# phMeter_v4_2.net
KiCad netlist of a schematic drawn in EAGLE
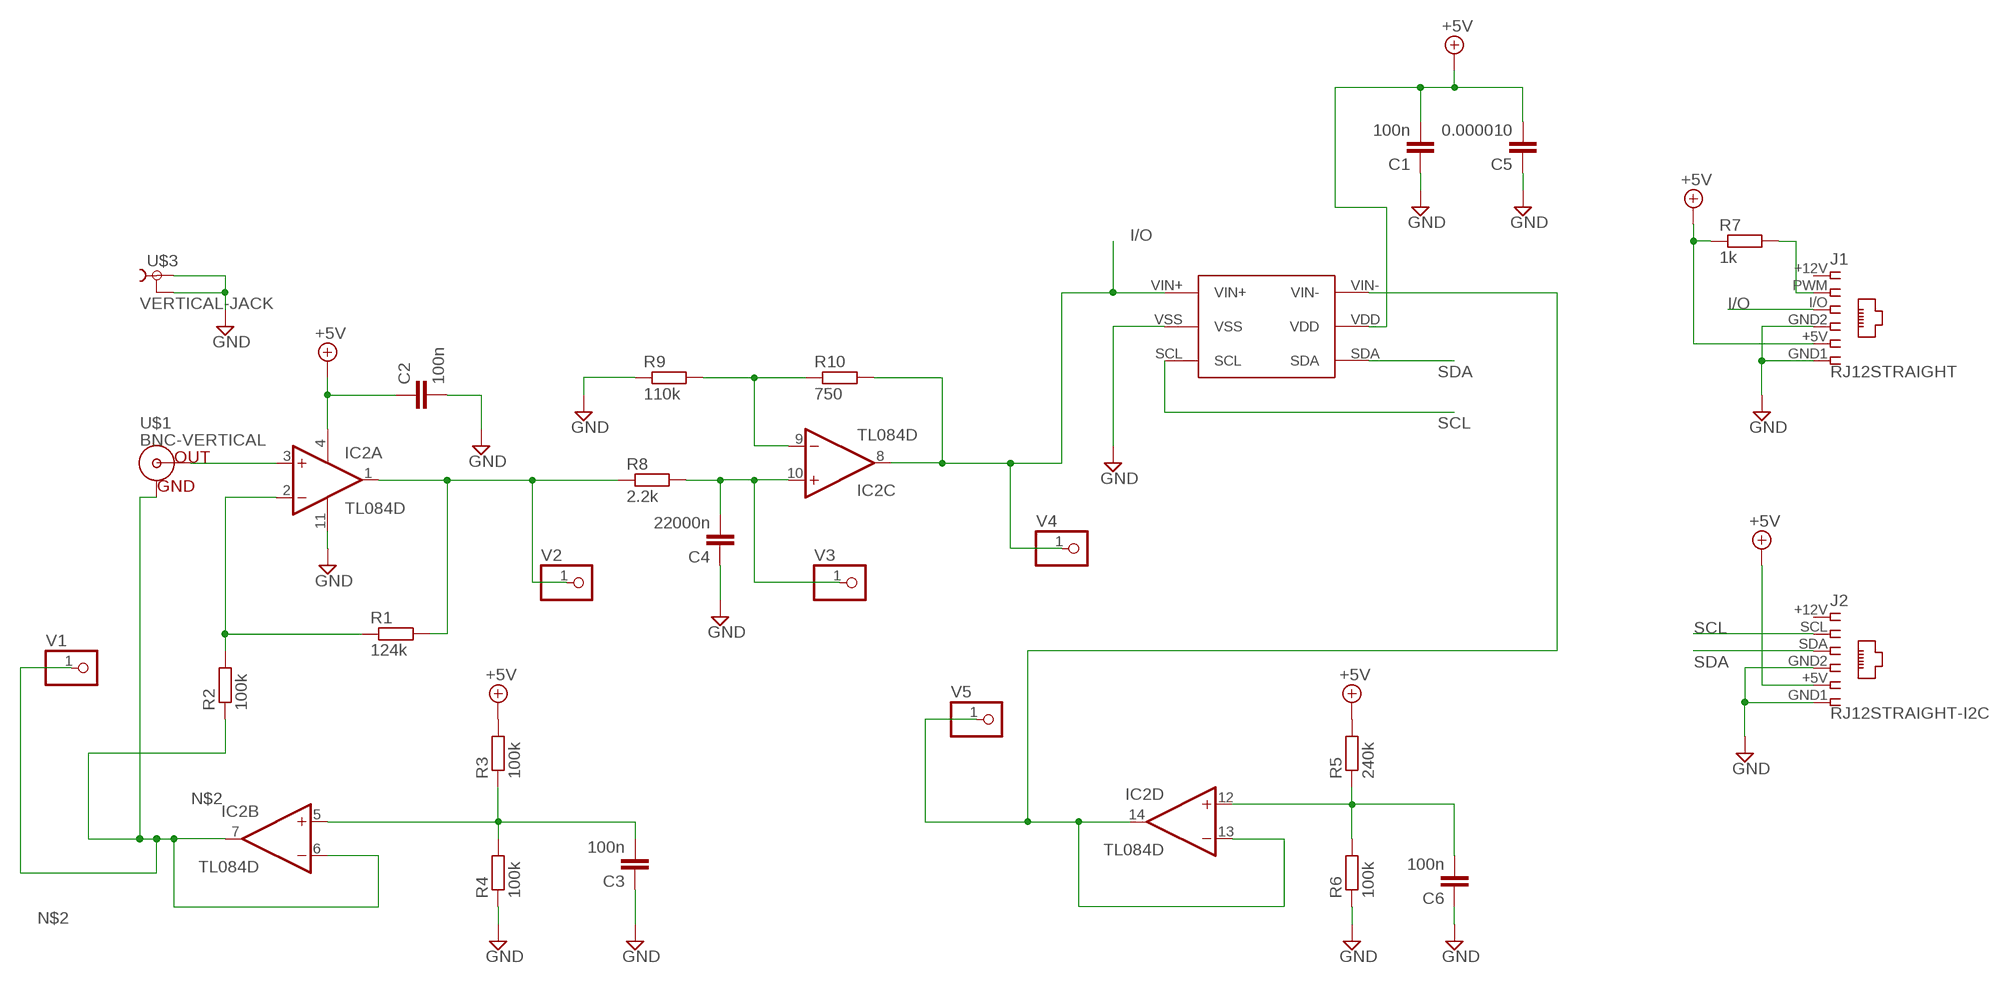
[diagram p0: schematic, sheet 1]

(export (version "E")
  (design (tool "Eeschema 10.0.6"))
  (components
    (comp (ref "C1")
      (value "100n")
      (footprint "eagle-import:C1206")
      (libsource (lib "eagle-import") (part "C-EUC1206"))
    )
    (comp (ref "C2")
      (value "100n")
      (footprint "eagle-import:C1206")
      (libsource (lib "eagle-import") (part "C-EUC1206"))
    )
    (comp (ref "C3")
      (value "100n")
      (footprint "eagle-import:C1206")
      (libsource (lib "eagle-import") (part "C-EUC1206"))
    )
    (comp (ref "C4")
      (value "22000n")
      (footprint "eagle-import:C1206")
      (libsource (lib "eagle-import") (part "C-EUC1206"))
    )
    (comp (ref "C5")
      (value "0.000010")
      (footprint "eagle-import:C1206")
      (libsource (lib "eagle-import") (part "C-EUC1206"))
    )
    (comp (ref "C6")
      (value "100n")
      (footprint "eagle-import:C1206")
      (libsource (lib "eagle-import") (part "C-EUC1206"))
    )
    (comp (ref "IC2")
      (value "TL084D")
      (footprint "eagle-import:SO14")
      (libsource (lib "eagle-import") (part "TL084D"))
    )
    (comp (ref "J1")
      (value "RJ12STRAIGHT")
      (footprint "eagle-import:RJ12-STRAIGHT")
      (libsource (lib "eagle-import") (part "RJ12STRAIGHT"))
    )
    (comp (ref "J2")
      (value "RJ12STRAIGHT-I2C")
      (footprint "eagle-import:RJ12-STRAIGHT-I2C")
      (libsource (lib "eagle-import") (part "RJ12STRAIGHT-I2C"))
    )
    (comp (ref "R1")
      (value "124k")
      (footprint "eagle-import:R1206")
      (libsource (lib "eagle-import") (part "R-EU_R1206"))
    )
    (comp (ref "R2")
      (value "100k")
      (footprint "eagle-import:R1206")
      (libsource (lib "eagle-import") (part "R-EU_R1206"))
    )
    (comp (ref "R3")
      (value "100k")
      (footprint "eagle-import:R1206")
      (libsource (lib "eagle-import") (part "R-EU_R1206"))
    )
    (comp (ref "R4")
      (value "100k")
      (footprint "eagle-import:R1206")
      (libsource (lib "eagle-import") (part "R-EU_R1206"))
    )
    (comp (ref "R5")
      (value "240k")
      (footprint "eagle-import:R1206")
      (libsource (lib "eagle-import") (part "R-EU_R1206"))
    )
    (comp (ref "R6")
      (value "100k")
      (footprint "eagle-import:R1206")
      (libsource (lib "eagle-import") (part "R-EU_R1206"))
    )
    (comp (ref "R7")
      (value "1k")
      (footprint "eagle-import:R1206")
      (libsource (lib "eagle-import") (part "R-EU_R1206"))
    )
    (comp (ref "R8")
      (value "2.2k")
      (footprint "eagle-import:R1206")
      (libsource (lib "eagle-import") (part "R-EU_R1206"))
    )
    (comp (ref "R9")
      (value "110k")
      (footprint "eagle-import:R1206")
      (libsource (lib "eagle-import") (part "R-EU_R1206"))
    )
    (comp (ref "R10")
      (value "750")
      (footprint "eagle-import:R1206")
      (libsource (lib "eagle-import") (part "R-EU_R1206"))
    )
    (comp (ref "U$1")
      (value "BNC-VERTICAL")
      (footprint "eagle-import:BNC-VERTICAL")
      (libsource (lib "eagle-import") (part "BNC-VERTICAL"))
    )
    (comp (ref "U$3")
      (value "VERTICAL-JACK")
      (footprint "eagle-import:VERTICAL-JACK")
      (libsource (lib "eagle-import") (part "VERTICAL-JACK"))
    )
    (comp (ref "U$5")
      (value "MCP3425")
      (footprint "eagle-import:SOT-23-6")
      (libsource (lib "eagle-import") (part "MCP3425"))
    )
    (comp (ref "V1")
      (value "PINHD-1X1")
      (footprint "eagle-import:1X01")
      (libsource (lib "eagle-import") (part "PINHD-1X1"))
    )
    (comp (ref "V2")
      (value "PINHD-1X1")
      (footprint "eagle-import:1X01")
      (libsource (lib "eagle-import") (part "PINHD-1X1"))
    )
    (comp (ref "V3")
      (value "PINHD-1X1")
      (footprint "eagle-import:1X01")
      (libsource (lib "eagle-import") (part "PINHD-1X1"))
    )
    (comp (ref "V4")
      (value "PINHD-1X1")
      (footprint "eagle-import:1X01")
      (libsource (lib "eagle-import") (part "PINHD-1X1"))
    )
    (comp (ref "V5")
      (value "PINHD-1X1")
      (footprint "eagle-import:1X01")
      (libsource (lib "eagle-import") (part "PINHD-1X1"))
    )
  )
  (nets
    (net (code "1") (name "+5V") (class "Default")
      (node (ref "C1") (pin "2") (pinfunction "2_2") (pintype "passive"))
      (node (ref "C2") (pin "1") (pinfunction "1_1") (pintype "passive"))
      (node (ref "C5") (pin "2") (pinfunction "2_2") (pintype "passive"))
      (node (ref "IC2") (pin "4") (pinfunction "V+_4") (pintype "power_in"))
      (node (ref "J1") (pin "+5V") (pinfunction "5_+5V") (pintype "bidirectional"))
      (node (ref "J2") (pin "+5V") (pinfunction "5_+5V") (pintype "bidirectional"))
      (node (ref "R3") (pin "2") (pinfunction "2_2") (pintype "passive"))
      (node (ref "R5") (pin "2") (pinfunction "2_2") (pintype "passive"))
      (node (ref "R7") (pin "1") (pinfunction "1_1") (pintype "passive"))
      (node (ref "U$5") (pin "VDD") (pinfunction "VDD_VDD") (pintype "bidirectional"))
    )
    (net (code "2") (name "/I{slash}O") (class "Default")
      (node (ref "IC2") (pin "8") (pinfunction "OUT_8") (pintype "output"))
      (node (ref "J1") (pin "I/O") (pinfunction "3_I/O") (pintype "bidirectional"))
      (node (ref "R10") (pin "2") (pinfunction "2_2") (pintype "passive"))
      (node (ref "U$5") (pin "VIN+") (pinfunction "VIN+_VIN+") (pintype "bidirectional"))
      (node (ref "V4") (pin "1") (pinfunction "1_1") (pintype "passive"))
    )
    (net (code "3") (name "/N$2") (class "Default")
      (node (ref "IC2") (pin "6") (pinfunction "-IN_6") (pintype "input"))
      (node (ref "IC2") (pin "7") (pinfunction "OUT_7") (pintype "output"))
      (node (ref "R2") (pin "1") (pinfunction "1_1") (pintype "passive"))
      (node (ref "U$1") (pin "G") (pinfunction "GND_G") (pintype "bidirectional"))
      (node (ref "V1") (pin "1") (pinfunction "1_1") (pintype "passive"))
    )
    (net (code "4") (name "/SCL") (class "Default")
      (node (ref "J2") (pin "SCL") (pinfunction "2_SCL") (pintype "bidirectional"))
      (node (ref "U$5") (pin "SCL") (pinfunction "SCL_SCL") (pintype "bidirectional"))
    )
    (net (code "5") (name "/SDA") (class "Default")
      (node (ref "J2") (pin "SDA") (pinfunction "3_SDA") (pintype "bidirectional"))
      (node (ref "U$5") (pin "SDA") (pinfunction "SDA_SDA") (pintype "bidirectional"))
    )
    (net (code "6") (name "GND") (class "Default")
      (node (ref "C1") (pin "1") (pinfunction "1_1") (pintype "passive"))
      (node (ref "C2") (pin "2") (pinfunction "2_2") (pintype "passive"))
      (node (ref "C3") (pin "1") (pinfunction "1_1") (pintype "passive"))
      (node (ref "C4") (pin "1") (pinfunction "1_1") (pintype "passive"))
      (node (ref "C5") (pin "1") (pinfunction "1_1") (pintype "passive"))
      (node (ref "C6") (pin "1") (pinfunction "1_1") (pintype "passive"))
      (node (ref "IC2") (pin "11") (pinfunction "V-_11") (pintype "power_in"))
      (node (ref "J1") (pin "GND1") (pinfunction "6_GND1") (pintype "bidirectional"))
      (node (ref "J1") (pin "GND2") (pinfunction "4_GND2") (pintype "bidirectional"))
      (node (ref "J2") (pin "GND1") (pinfunction "6_GND1") (pintype "bidirectional"))
      (node (ref "J2") (pin "GND2") (pinfunction "4_GND2") (pintype "bidirectional"))
      (node (ref "R4") (pin "1") (pinfunction "1_1") (pintype "passive"))
      (node (ref "R6") (pin "1") (pinfunction "1_1") (pintype "passive"))
      (node (ref "R9") (pin "1") (pinfunction "1_1") (pintype "passive"))
      (node (ref "U$3") (pin "P$1") (pinfunction "1_P$1") (pintype "passive"))
      (node (ref "U$3") (pin "P$2") (pinfunction "2_P$2") (pintype "passive"))
      (node (ref "U$5") (pin "VSS") (pinfunction "VSS_VSS") (pintype "bidirectional"))
    )
    (net (code "7") (name "Net-(IC2A-+IN)") (class "Default")
      (node (ref "IC2") (pin "3") (pinfunction "+IN_3") (pintype "input"))
      (node (ref "U$1") (pin "S") (pinfunction "OUT_S") (pintype "bidirectional"))
    )
    (net (code "8") (name "Net-(IC2A--IN)") (class "Default")
      (node (ref "IC2") (pin "2") (pinfunction "-IN_2") (pintype "input"))
      (node (ref "R1") (pin "1") (pinfunction "1_1") (pintype "passive"))
      (node (ref "R2") (pin "2") (pinfunction "2_2") (pintype "passive"))
    )
    (net (code "9") (name "Net-(IC2A-OUT)") (class "Default")
      (node (ref "IC2") (pin "1") (pinfunction "OUT_1") (pintype "output"))
      (node (ref "R1") (pin "2") (pinfunction "2_2") (pintype "passive"))
      (node (ref "R8") (pin "1") (pinfunction "1_1") (pintype "passive"))
      (node (ref "V2") (pin "1") (pinfunction "1_1") (pintype "passive"))
    )
    (net (code "10") (name "Net-(IC2B-+IN)") (class "Default")
      (node (ref "C3") (pin "2") (pinfunction "2_2") (pintype "passive"))
      (node (ref "IC2") (pin "5") (pinfunction "+IN_5") (pintype "input"))
      (node (ref "R3") (pin "1") (pinfunction "1_1") (pintype "passive"))
      (node (ref "R4") (pin "2") (pinfunction "2_2") (pintype "passive"))
    )
    (net (code "11") (name "Net-(IC2C-+IN)") (class "Default")
      (node (ref "C4") (pin "2") (pinfunction "2_2") (pintype "passive"))
      (node (ref "IC2") (pin "10") (pinfunction "+IN_10") (pintype "input"))
      (node (ref "R8") (pin "2") (pinfunction "2_2") (pintype "passive"))
      (node (ref "V3") (pin "1") (pinfunction "1_1") (pintype "passive"))
    )
    (net (code "12") (name "Net-(IC2C--IN)") (class "Default")
      (node (ref "IC2") (pin "9") (pinfunction "-IN_9") (pintype "input"))
      (node (ref "R10") (pin "1") (pinfunction "1_1") (pintype "passive"))
      (node (ref "R9") (pin "2") (pinfunction "2_2") (pintype "passive"))
    )
    (net (code "13") (name "Net-(IC2D-+IN)") (class "Default")
      (node (ref "C6") (pin "2") (pinfunction "2_2") (pintype "passive"))
      (node (ref "IC2") (pin "12") (pinfunction "+IN_12") (pintype "input"))
      (node (ref "R5") (pin "1") (pinfunction "1_1") (pintype "passive"))
      (node (ref "R6") (pin "2") (pinfunction "2_2") (pintype "passive"))
    )
    (net (code "14") (name "Net-(IC2D--IN)") (class "Default")
      (node (ref "IC2") (pin "13") (pinfunction "-IN_13") (pintype "input"))
      (node (ref "IC2") (pin "14") (pinfunction "OUT_14") (pintype "output"))
      (node (ref "U$5") (pin "VIN-") (pinfunction "VIN-_VIN-") (pintype "bidirectional"))
      (node (ref "V5") (pin "1") (pinfunction "1_1") (pintype "passive"))
    )
    (net (code "15") (name "Net-(J1-2)") (class "Default")
      (node (ref "J1") (pin "PWM") (pinfunction "2_PWM") (pintype "bidirectional"))
      (node (ref "R7") (pin "2") (pinfunction "2_2") (pintype "passive"))
    )
    (net (code "16") (name "unconnected-(J1-1-Pad+12V)") (class "Default")
      (node (ref "J1") (pin "+12V") (pinfunction "1_+12V") (pintype "bidirectional"))
    )
    (net (code "17") (name "unconnected-(J2-1-Pad+12V)") (class "Default")
      (node (ref "J2") (pin "+12V") (pinfunction "1_+12V") (pintype "bidirectional"))
    )
  )
)
